# 20813.net
KiCad netlist of a schematic drawn in Altium Designer
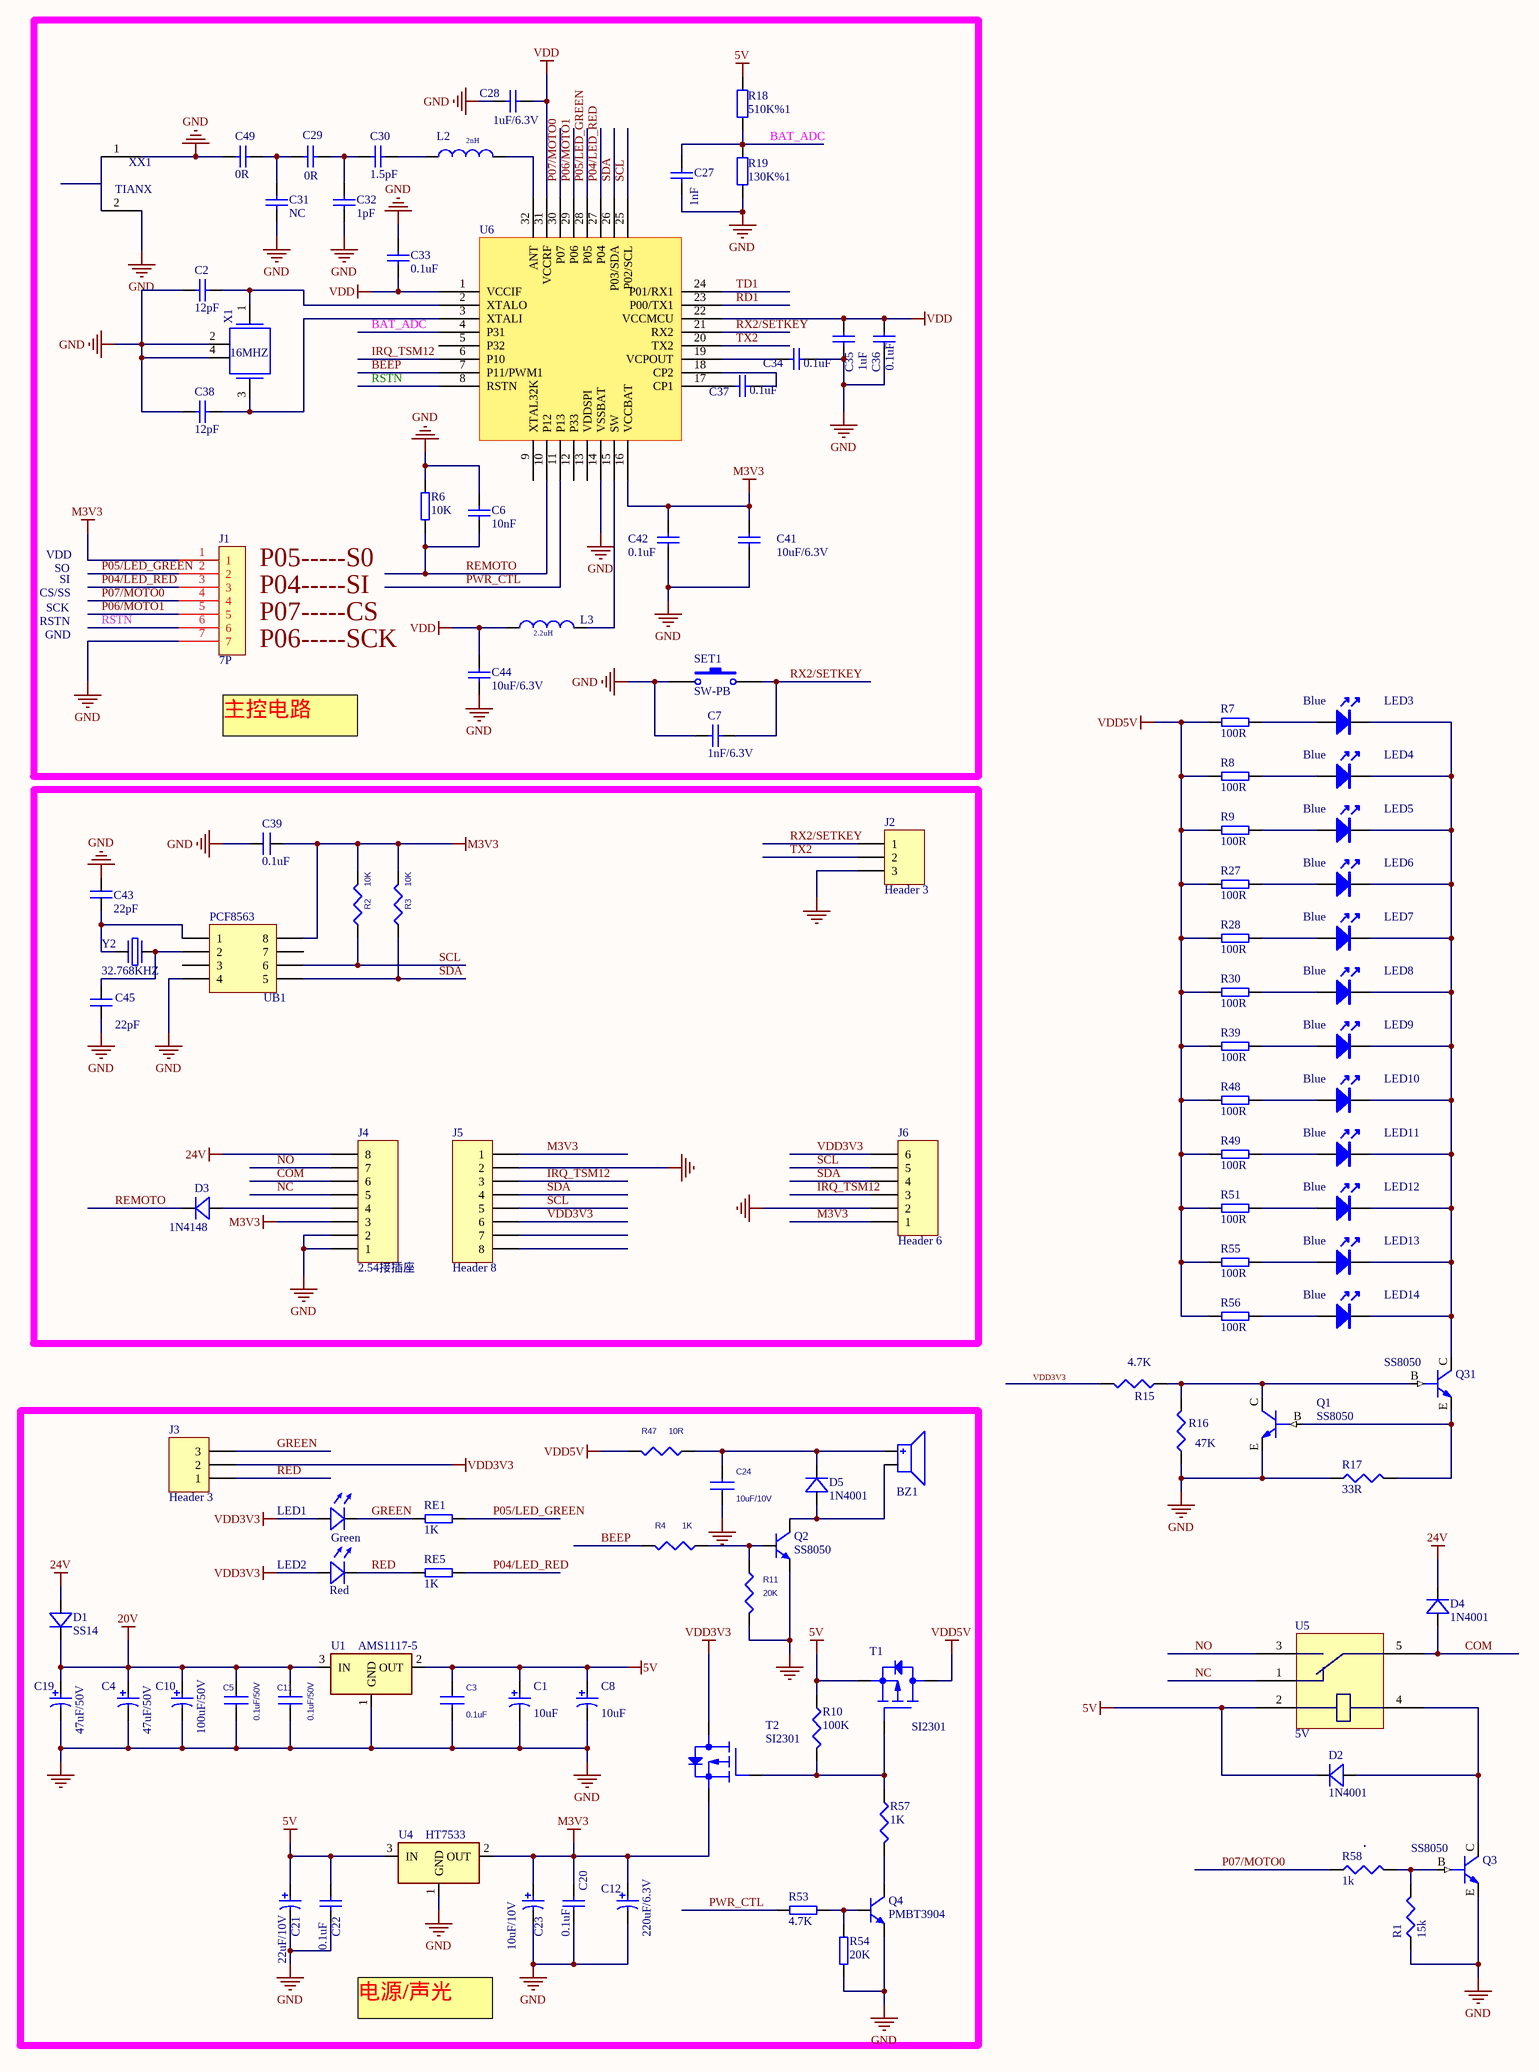
[diagram p0: 天地通门禁20813.SchDoc]

(export (version "E")
  (design (tool "Eeschema 10.0.6"))
  (components
    (comp (ref "BZ1")
      (value "BUZZER")
      (footprint "BUZZ_EN")
      (description "Buzzer")
      (libsource (lib "MyLibrary") (part "BUZZER"))
    )
    (comp (ref "C1")
      (value "10uF")
      (footprint "R6.3*5.8")
      (description "Capacitor, tolerance ±20%")
      (libsource (lib "MySchLib") (part "CAP-P"))
    )
    (comp (ref "C2")
      (value "12pF")
      (footprint "0603C")
      (description "Capacitor")
      (fields (field (name "PUBLISHER") "Altium Limited"))
      (libsource (lib "MySchlib") (part "Cap"))
    )
    (comp (ref "C3") (value "0.1uF") (footprint "0603C") (libsource (lib "*") (part "CAP NP")))
    (comp (ref "C4")
      (value "47uF/50V")
      (footprint "R6.3*7.7")
      (description "Capacitor, tolerance ±20%")
      (libsource (lib "MySchLib") (part "CAP-P"))
    )
    (comp (ref "C5") (value "0.1uF/50V") (footprint "0805C") (libsource (lib "*") (part "CAP NP")))
    (comp (ref "C6")
      (value "10nF")
      (footprint "0603C")
      (description "Capacitor")
      (fields (field (name "PUBLISHER") "Altium Limited"))
      (libsource (lib "MySchlib") (part "Cap"))
    )
    (comp (ref "C7")
      (value "1nF/6.3V")
      (footprint "0603C")
      (description "Capacitor")
      (fields (field (name "PUBLISHER") "Altium Limited"))
      (libsource (lib "MySchlib") (part "Cap"))
    )
    (comp (ref "C8")
      (value "10uF")
      (footprint "0805C")
      (description "Capacitor, tolerance ±20%")
      (libsource (lib "MySchLib") (part "CAP-P"))
    )
    (comp (ref "C10")
      (value "100uF/50V")
      (footprint "R6.3*7.7")
      (description "Capacitor, tolerance ±20%")
      (libsource (lib "MySchLib") (part "CAP-P"))
    )
    (comp (ref "C11") (value "0.1uF/50V") (footprint "0805C") (libsource (lib "*") (part "CAP NP")))
    (comp (ref "C12")
      (value "220uF/6.3V")
      (footprint "R6.3*5.8")
      (description "Capacitor, tolerance ±20%")
      (libsource (lib "MySchLib") (part "CAP-P"))
    )
    (comp (ref "C19")
      (value "47uF/50V")
      (footprint "R6.3*7.7")
      (description "Capacitor, tolerance ±20%")
      (libsource (lib "MySchLib") (part "CAP-P"))
    )
    (comp (ref "C20")
      (value "0.1uF")
      (footprint "0603C")
      (description "Capacitor, Ceramic")
      (fields (field (name "TOLERANCE") "5 %"))
      (libsource (lib "MyLibrary") (part "CAP-NP"))
    )
    (comp (ref "C21")
      (value "22uF/10V")
      (footprint "0805C")
      (description "Capacitor, tolerance ±20%")
      (libsource (lib "MySchLib") (part "CAP-P"))
    )
    (comp (ref "C22")
      (value "0.1uF")
      (footprint "0603C")
      (description "Capacitor, Ceramic")
      (fields (field (name "TOLERANCE") "5 %"))
      (libsource (lib "MyLibrary") (part "CAP-NP"))
    )
    (comp (ref "C23")
      (value "10uF/10V")
      (footprint "0805C")
      (description "Capacitor, tolerance ±20%")
      (libsource (lib "MySchLib") (part "CAP-P"))
    )
    (comp (ref "C24") (value "10uF/10V") (footprint "0805C") (libsource (lib "*") (part "C_0_Dup1")))
    (comp (ref "C27")
      (value "1nF")
      (footprint "0603C")
      (description "Capacitor, Ceramic")
      (fields (field (name "TOLERANCE") "5 %"))
      (libsource (lib "MyLibrary") (part "CAP-NP"))
    )
    (comp (ref "C28")
      (value "1uF/6.3V")
      (footprint "0603C")
      (description "Capacitor")
      (fields (field (name "PUBLISHER") "Altium Limited"))
      (libsource (lib "MySchlib") (part "Cap"))
    )
    (comp (ref "C29")
      (value "0R")
      (footprint "0603C")
      (description "Capacitor")
      (fields (field (name "PUBLISHER") "Altium Limited"))
      (libsource (lib "MySchlib") (part "Cap"))
    )
    (comp (ref "C30")
      (value "1.5pF")
      (footprint "0603C")
      (description "Capacitor")
      (fields (field (name "PUBLISHER") "Altium Limited"))
      (libsource (lib "MySchlib") (part "Cap"))
    )
    (comp (ref "C31")
      (value "NC")
      (footprint "0603C")
      (description "Capacitor")
      (fields (field (name "PUBLISHER") "Altium Limited"))
      (libsource (lib "MySchlib") (part "Cap"))
    )
    (comp (ref "C32")
      (value "1pF")
      (footprint "0603C")
      (description "Capacitor")
      (fields (field (name "PUBLISHER") "Altium Limited"))
      (libsource (lib "MySchlib") (part "Cap"))
    )
    (comp (ref "C33")
      (value "0.1uF")
      (footprint "0603C")
      (description "Capacitor")
      (fields (field (name "PUBLISHER") "Altium Limited"))
      (libsource (lib "MySchlib") (part "Cap"))
    )
    (comp (ref "C34")
      (value "0.1uF")
      (footprint "0603C")
      (description "Capacitor")
      (fields (field (name "PUBLISHER") "Altium Limited"))
      (libsource (lib "MySchlib") (part "Cap"))
    )
    (comp (ref "C35")
      (value "1uF")
      (footprint "0603C")
      (description "Capacitor")
      (fields (field (name "PUBLISHER") "Altium Limited"))
      (libsource (lib "MySchlib") (part "Cap"))
    )
    (comp (ref "C36")
      (value "0.1uF")
      (footprint "0603C")
      (description "Capacitor")
      (fields (field (name "PUBLISHER") "Altium Limited"))
      (libsource (lib "MySchlib") (part "Cap"))
    )
    (comp (ref "C37")
      (value "0.1uF")
      (footprint "0603C")
      (description "Capacitor")
      (fields (field (name "PUBLISHER") "Altium Limited"))
      (libsource (lib "MySchlib") (part "Cap"))
    )
    (comp (ref "C38")
      (value "12pF")
      (footprint "0603C")
      (description "Capacitor")
      (fields (field (name "PUBLISHER") "Altium Limited"))
      (libsource (lib "MySchlib") (part "Cap"))
    )
    (comp (ref "C39") (value "0.1uF") (footprint "0603C") (libsource (lib "自建元件库") (part "C")))
    (comp (ref "C41")
      (value "10uF/6.3V")
      (footprint "0603C")
      (description "Capacitor")
      (fields (field (name "PUBLISHER") "Altium Limited"))
      (libsource (lib "MySchlib") (part "Cap"))
    )
    (comp (ref "C42")
      (value "0.1uF")
      (footprint "0603C")
      (description "Capacitor")
      (fields (field (name "PUBLISHER") "Altium Limited"))
      (libsource (lib "MySchlib") (part "Cap"))
    )
    (comp (ref "C43") (value "22pF") (footprint "0603C") (libsource (lib "自建元件库") (part "C")))
    (comp (ref "C44")
      (value "10uF/6.3V")
      (footprint "0603C")
      (description "Capacitor")
      (fields (field (name "PUBLISHER") "Altium Limited"))
      (libsource (lib "MySchlib") (part "Cap"))
    )
    (comp (ref "C45") (value "22pF") (footprint "0603C") (libsource (lib "自建元件库") (part "C")))
    (comp (ref "C49")
      (value "0R")
      (footprint "0603C")
      (description "Capacitor")
      (fields (field (name "PUBLISHER") "Altium Limited"))
      (libsource (lib "MySchlib") (part "Cap"))
    )
    (comp (ref "D1") (value "SS14") (footprint "DO-214AA") (libsource (lib "") (part "D_1")))
    (comp (ref "D2") (value "1N4001") (footprint "M7") (libsource (lib "MySch") (part "D")))
    (comp (ref "D3") (value "1N4148") (footprint "SOD-123") (libsource (lib "") (part "D_1")))
    (comp (ref "D4") (value "1N4001") (footprint "M7") (libsource (lib "MySch") (part "D")))
    (comp (ref "D5") (value "1N4001") (footprint "M7") (libsource (lib "MySch") (part "D")))
    (comp (ref "J1") (value "7P") (footprint "7P-2.0MM") (libsource (lib "保险箱STM32") (part "7P")))
    (comp (ref "J2")
      (value "Header 3")
      (footprint "3P-2.0MM")
      (description "Header, 3-Pin")
      (fields (field (name "PUBLISHER") "Altium Limited"))
      (libsource (lib "Miscellaneous Connectors") (part "Header 3"))
    )
    (comp (ref "J3")
      (value "Header 3")
      (footprint "3PIN-2.0")
      (description "Header, 3-Pin")
      (fields (field (name "PUBLISHER") "Altium Limited"))
      (libsource (lib "") (part "Header 3_1"))
    )
    (comp (ref "J4")
      (value "2.54接插座")
      (footprint "2.54螺丝接线座8P")
      (description "Header, 8-Pin")
      (fields (field (name "PUBLISHER") "Altium Limited"))
      (libsource (lib "") (part "Header 8_1"))
    )
    (comp (ref "J5")
      (value "Header 8")
      (footprint "8P-1.25mm")
      (description "Header, 8-Pin")
      (fields (field (name "PUBLISHER") "Altium Limited"))
      (libsource (lib "Miscellaneous Connectors") (part "Header 8"))
    )
    (comp (ref "J6")
      (value "Header 6")
      (footprint "6P-1.25mm")
      (description "Header, 6-Pin")
      (fields (field (name "PUBLISHER") "Altium Limited"))
      (libsource (lib "Miscellaneous Connectors") (part "Header 6"))
    )
    (comp (ref "L2")
      (value "2nH")
      (footprint "0603L")
      (description "Power Inductor, 4.7uH, 0.7A, 260mR DCR")
      (fields
        (field (name "XMOS PART NUMBER") "E-09-0011")
        (field (name "MANUFACTURER") "Taiyo Yuden")
        (field (name "PART CREATOR") "JG")
        (field (name "APPROVED") "NO")
      )
      (libsource (lib "MySchlib") (part "INDUCTOR"))
    )
    (comp (ref "L3")
      (value "2.2uH")
      (footprint "0603L")
      (description "Power Inductor, 4.7uH, 0.7A, 260mR DCR")
      (fields
        (field (name "XMOS PART NUMBER") "E-09-0011")
        (field (name "MANUFACTURER") "Taiyo Yuden")
        (field (name "PART CREATOR") "JG")
        (field (name "APPROVED") "NO")
      )
      (libsource (lib "MySchlib") (part "INDUCTOR"))
    )
    (comp (ref "LED1") (value "Green") (footprint "0805LED") (libsource (lib "MyLibrary") (part "LED")))
    (comp (ref "LED2") (value "Red") (footprint "0805LED") (libsource (lib "MyLibrary") (part "LED")))
    (comp (ref "LED3") (value "Blue") (footprint "0805LED") (libsource (lib "*") (part "LED")))
    (comp (ref "LED4") (value "Blue") (footprint "0805LED") (libsource (lib "*") (part "LED")))
    (comp (ref "LED5") (value "Blue") (footprint "0805LED") (libsource (lib "*") (part "LED")))
    (comp (ref "LED6") (value "Blue") (footprint "0805LED") (libsource (lib "*") (part "LED")))
    (comp (ref "LED7") (value "Blue") (footprint "0805LED") (libsource (lib "*") (part "LED")))
    (comp (ref "LED8") (value "Blue") (footprint "0805LED") (libsource (lib "*") (part "LED")))
    (comp (ref "LED9") (value "Blue") (footprint "0805LED") (libsource (lib "*") (part "LED")))
    (comp (ref "LED10") (value "Blue") (footprint "0805LED") (libsource (lib "*") (part "LED")))
    (comp (ref "LED11") (value "Blue") (footprint "0805LED") (libsource (lib "*") (part "LED")))
    (comp (ref "LED12") (value "Blue") (footprint "0805LED") (libsource (lib "*") (part "LED")))
    (comp (ref "LED13") (value "Blue") (footprint "0805LED") (libsource (lib "*") (part "LED")))
    (comp (ref "LED14") (value "Blue") (footprint "0805LED") (libsource (lib "*") (part "LED")))
    (comp (ref "Q1") (value "SS8050") (footprint "SOT-23 - BCE") (libsource (lib "*") (part "PMBT3904")))
    (comp (ref "Q2")
      (value "SS8050")
      (footprint "SOT-23-3L")
      (description "Bipolar Junction Transistor")
      (libsource (lib "MyLibrary") (part "NPN_BJT"))
    )
    (comp (ref "Q3") (value "SS8050") (footprint "SOT-23 - BCE") (libsource (lib "*") (part "PMBT3904")))
    (comp (ref "Q4")
      (value "PMBT3904")
      (footprint "SOT-23-3L")
      (description "Bipolar Junction Transistor")
      (libsource (lib "MyLibrary") (part "NPN_BJT"))
    )
    (comp (ref "Q31") (value "SS8050") (footprint "SOT-23 - BCE") (libsource (lib "*") (part "PMBT3904")))
    (comp (ref "R1") (value "15k") (footprint "0603R") (libsource (lib "*") (part "R")))
    (comp (ref "R2") (value "10K") (footprint "0603R") (libsource (lib "*") (part "RES")))
    (comp (ref "R3") (value "10K") (footprint "0603R") (libsource (lib "*") (part "RES")))
    (comp (ref "R4") (value "1K") (footprint "0603R") (libsource (lib "*") (part "R_Dup1")))
    (comp (ref "R6") (value "10K") (footprint "0603R") (libsource (lib "MySch") (part "R")))
    (comp (ref "R7") (value "100R") (footprint "0603R") (libsource (lib "MySch") (part "R")))
    (comp (ref "R8") (value "100R") (footprint "0603R") (libsource (lib "MySch") (part "R")))
    (comp (ref "R9") (value "100R") (footprint "0603R") (libsource (lib "MySch") (part "R")))
    (comp (ref "R10") (value "100K") (footprint "0603R") (libsource (lib "*") (part "R")))
    (comp (ref "R11") (value "20K") (footprint "0603R") (libsource (lib "*") (part "R_Dup1")))
    (comp (ref "R15") (value "4.7K") (footprint "0603R") (libsource (lib "*") (part "R")))
    (comp (ref "R16") (value "47K") (footprint "0603R") (libsource (lib "*") (part "R")))
    (comp (ref "R17") (value "33R") (footprint "0603R") (libsource (lib "*") (part "R")))
    (comp (ref "R18")
      (value "510K%1")
      (footprint "0603R")
      (description "Resistor")
      (libsource (lib "MyLibrary") (part "Res2"))
    )
    (comp (ref "R19")
      (value "130K%1")
      (footprint "0603R")
      (description "Resistor")
      (libsource (lib "MyLibrary") (part "Res2"))
    )
    (comp (ref "R27") (value "100R") (footprint "0603R") (libsource (lib "MySch") (part "R")))
    (comp (ref "R28") (value "100R") (footprint "0603R") (libsource (lib "MySch") (part "R")))
    (comp (ref "R30") (value "100R") (footprint "0603R") (libsource (lib "MySch") (part "R")))
    (comp (ref "R39") (value "100R") (footprint "0603R") (libsource (lib "MySch") (part "R")))
    (comp (ref "R47") (value "10R") (footprint "0603R") (libsource (lib "*") (part "R_Dup1")))
    (comp (ref "R48") (value "100R") (footprint "0603R") (libsource (lib "MySch") (part "R")))
    (comp (ref "R49") (value "100R") (footprint "0603R") (libsource (lib "MySch") (part "R")))
    (comp (ref "R51") (value "100R") (footprint "0603R") (libsource (lib "MySch") (part "R")))
    (comp (ref "R53") (value "4.7K") (footprint "0603R") (libsource (lib "MySch") (part "R")))
    (comp (ref "R54") (value "20K") (footprint "0603R") (libsource (lib "MySch") (part "R")))
    (comp (ref "R55") (value "100R") (footprint "0603R") (libsource (lib "MySch") (part "R")))
    (comp (ref "R56") (value "100R") (footprint "0603R") (libsource (lib "MySch") (part "R")))
    (comp (ref "R57") (value "1K") (footprint "0603R") (libsource (lib "*") (part "R")))
    (comp (ref "R58") (value "1k") (footprint "0603R") (libsource (lib "*") (part "R")))
    (comp (ref "RE1") (value "1K") (footprint "0603R") (libsource (lib "MySch") (part "R")))
    (comp (ref "RE5") (value "1K") (footprint "0603R") (libsource (lib "MySch") (part "R")))
    (comp (ref "SET1")
      (value "SW-PB")
      (footprint "KEY-S")
      (description "Switch")
      (fields (field (name "PUBLISHER") "Altium Limited"))
      (libsource (lib "Miscellaneous Devices") (part "SW-PB"))
    )
    (comp (ref "T1")
      (value "SI2301")
      (footprint "SOT-23 - GDS")
      (libsource (lib "*") (part "PWRMOSFET_EP_DGS_0"))
    )
    (comp (ref "T2")
      (value "SI2301")
      (footprint "SOT-23 - GDS")
      (libsource (lib "*") (part "PWRMOSFET_EP_DGS_0"))
    )
    (comp (ref "U1") (value "AMS1117-5") (footprint "SOT223_M") (libsource (lib "*") (part "XC6206P302M")))
    (comp (ref "U4") (value "HT7533") (footprint "SOT-23-3L") (libsource (lib "*") (part "XC6206P302M")))
    (comp (ref "U5") (value "5V") (footprint "继电器1x") (libsource (lib "MYSchlib") (part "OMRON_G8P-1A4P")))
    (comp (ref "U6")
      (value "BK3431Q")
      (footprint "QFN32_4*4*0.4")
      (libsource (lib "BK3431") (part "BK3431Q"))
    )
    (comp (ref "UB1") (value "PCF8563") (footprint "SOP8") (libsource (lib "MySch") (part "IC8")))
    (comp (ref "X1")
      (value "16MHZ")
      (footprint "XTAL3225")
      (fields
        (field (name "XMOS PART NUMBER") "E-07-0030")
        (field (name "MANUFACTURER") "Abracon")
        (field (name "MANUFACTURER PART NUMBER") "ABLS-24.000MHz-B4")
        (field (name "PART CREATOR") "JG")
        (field (name "APPROVED") "NO")
      )
      (libsource (lib "MySchlib") (part "OSC"))
    )
    (comp (ref "XX1")
      (value "TIANX")
      (footprint "BT_NAMI_1")
      (libsource (lib "885阿里云PCB_Project1") (part "TIANX"))
    )
    (comp (ref "Y2") (value "32.768KHZ") (footprint "晶振-9") (libsource (lib "MySch") (part "晶振")))
  )
  (nets
    (net (code "1") (name "/BAT_ADC") (class "Default")
      (node (ref "C27") (pin "2") (pinfunction "2_2") (pintype "passive"))
      (node (ref "R18") (pin "2") (pinfunction "2_2") (pintype "passive"))
      (node (ref "R19") (pin "1") (pinfunction "1_1") (pintype "passive"))
      (node (ref "U6") (pin "4") (pinfunction "P31_4") (pintype "passive"))
    )
    (net (code "2") (name "/BEEP") (class "Default")
      (node (ref "R4") (pin "2") (pinfunction "2_2") (pintype "passive"))
      (node (ref "U6") (pin "7") (pinfunction "P11/PWM1_7") (pintype "passive"))
    )
    (net (code "3") (name "/COM") (class "Default")
      (node (ref "D4") (pin "A") (pinfunction "K_A") (pintype "passive"))
      (node (ref "J4") (pin "6") (pinfunction "6_6") (pintype "passive"))
      (node (ref "U5") (pin "5") (pinfunction "5_5") (pintype "passive"))
    )
    (net (code "4") (name "/GREEN") (class "Default")
      (node (ref "J3") (pin "3") (pinfunction "3_3") (pintype "passive"))
      (node (ref "LED1") (pin "2") (pinfunction "K_2") (pintype "passive"))
      (node (ref "RE1") (pin "1") (pintype "passive"))
    )
    (net (code "5") (name "/IRQ_TSM12") (class "Default")
      (node (ref "J5") (pin "3") (pinfunction "3_3") (pintype "passive"))
      (node (ref "J6") (pin "3") (pinfunction "3_3") (pintype "passive"))
      (node (ref "U6") (pin "6") (pinfunction "P10_6") (pintype "passive"))
    )
    (net (code "6") (name "/NC") (class "Default")
      (node (ref "J4") (pin "5") (pinfunction "5_5") (pintype "passive"))
      (node (ref "U5") (pin "1") (pinfunction "1_1") (pintype "passive"))
    )
    (net (code "7") (name "/NO") (class "Default")
      (node (ref "J4") (pin "7") (pinfunction "7_7") (pintype "passive"))
      (node (ref "U5") (pin "3") (pinfunction "3_3") (pintype "passive"))
    )
    (net (code "8") (name "/P04{slash}LED_RED") (class "Default")
      (node (ref "J1") (pin "3") (pinfunction "3_3") (pintype "passive"))
      (node (ref "RE5") (pin "2") (pintype "passive"))
      (node (ref "U6") (pin "27") (pinfunction "P04_27") (pintype "passive"))
    )
    (net (code "9") (name "/P05{slash}LED_GREEN") (class "Default")
      (node (ref "J1") (pin "2") (pinfunction "2_2") (pintype "passive"))
      (node (ref "RE1") (pin "2") (pintype "passive"))
      (node (ref "U6") (pin "28") (pinfunction "P05_28") (pintype "passive"))
    )
    (net (code "10") (name "/P06{slash}MOTO1") (class "Default")
      (node (ref "J1") (pin "5") (pinfunction "5_5") (pintype "passive"))
      (node (ref "U6") (pin "29") (pinfunction "P06_29") (pintype "passive"))
    )
    (net (code "11") (name "/P07{slash}MOTO0") (class "Default")
      (node (ref "J1") (pin "4") (pinfunction "4_4") (pintype "passive"))
      (node (ref "R58") (pin "1") (pinfunction "1_1") (pintype "passive"))
      (node (ref "U6") (pin "30") (pinfunction "P07_30") (pintype "passive"))
    )
    (net (code "12") (name "/PWR_CTL") (class "Default")
      (node (ref "R53") (pin "1") (pintype "passive"))
      (node (ref "U6") (pin "11") (pinfunction "P13_11") (pintype "passive"))
    )
    (net (code "13") (name "/RD1") (class "Default")
      (node (ref "U6") (pin "23") (pinfunction "P00/TX1_23") (pintype "passive"))
    )
    (net (code "14") (name "/RED") (class "Default")
      (node (ref "J3") (pin "1") (pinfunction "1_1") (pintype "passive"))
      (node (ref "LED2") (pin "2") (pinfunction "K_2") (pintype "passive"))
      (node (ref "RE5") (pin "1") (pintype "passive"))
    )
    (net (code "15") (name "/REMOTO") (class "Default")
      (node (ref "C6") (pin "2") (pinfunction "2_2") (pintype "passive"))
      (node (ref "D3") (pin "2") (pinfunction "K_2") (pintype "passive"))
      (node (ref "R6") (pin "1") (pintype "passive"))
      (node (ref "U6") (pin "10") (pinfunction "P12_10") (pintype "passive"))
    )
    (net (code "16") (name "/RSTN") (class "Default")
      (node (ref "J1") (pin "6") (pinfunction "6_6") (pintype "passive"))
      (node (ref "U6") (pin "8") (pinfunction "RSTN_8") (pintype "passive"))
    )
    (net (code "17") (name "/RX2{slash}SETKEY") (class "Default")
      (node (ref "C7") (pin "1") (pinfunction "1_1") (pintype "passive"))
      (node (ref "J2") (pin "1") (pinfunction "1_1") (pintype "passive"))
      (node (ref "SET1") (pin "2") (pinfunction "2_2") (pintype "passive"))
      (node (ref "U6") (pin "21") (pinfunction "RX2_21") (pintype "passive"))
    )
    (net (code "18") (name "/SCL") (class "Default")
      (node (ref "J5") (pin "5") (pinfunction "5_5") (pintype "passive"))
      (node (ref "J6") (pin "5") (pinfunction "5_5") (pintype "passive"))
      (node (ref "R2") (pin "2") (pinfunction "2_2") (pintype "passive"))
      (node (ref "U6") (pin "25") (pinfunction "P02/SCL_25") (pintype "passive"))
      (node (ref "UB1") (pin "6") (pinfunction "6_6") (pintype "passive"))
    )
    (net (code "19") (name "/SDA") (class "Default")
      (node (ref "J5") (pin "4") (pinfunction "4_4") (pintype "passive"))
      (node (ref "J6") (pin "4") (pinfunction "4_4") (pintype "passive"))
      (node (ref "R3") (pin "2") (pinfunction "2_2") (pintype "passive"))
      (node (ref "U6") (pin "26") (pinfunction "P03/SDA_26") (pintype "passive"))
      (node (ref "UB1") (pin "5") (pinfunction "5_5") (pintype "passive"))
    )
    (net (code "20") (name "/TD1") (class "Default")
      (node (ref "U6") (pin "24") (pinfunction "P01/RX1_24") (pintype "passive"))
    )
    (net (code "21") (name "/TX2") (class "Default")
      (node (ref "J2") (pin "2") (pinfunction "2_2") (pintype "passive"))
      (node (ref "U6") (pin "20") (pinfunction "TX2_20") (pintype "passive"))
    )
    (net (code "22") (name "5V") (class "Default")
      (node (ref "C1") (pin "1") (pinfunction "1_1") (pintype "passive"))
      (node (ref "C21") (pin "1") (pinfunction "1_1") (pintype "passive"))
      (node (ref "C22") (pin "1") (pinfunction "1_1") (pintype "passive"))
      (node (ref "C3") (pin "1") (pinfunction "1_1") (pintype "passive"))
      (node (ref "C8") (pin "1") (pinfunction "1_1") (pintype "passive"))
      (node (ref "D2") (pin "K") (pinfunction "A_K") (pintype "passive"))
      (node (ref "R10") (pin "1") (pinfunction "1_1") (pintype "passive"))
      (node (ref "R18") (pin "1") (pinfunction "1_1") (pintype "passive"))
      (node (ref "T1") (pin "S") (pinfunction "SOURCE_S") (pintype "passive"))
      (node (ref "U1") (pin "2") (pinfunction "OUT_2") (pintype "passive"))
      (node (ref "U4") (pin "3") (pinfunction "IN_3") (pintype "passive"))
      (node (ref "U5") (pin "2") (pinfunction "2_2") (pintype "passive"))
    )
    (net (code "23") (name "20V") (class "Default")
      (node (ref "C10") (pin "1") (pinfunction "1_1") (pintype "passive"))
      (node (ref "C11") (pin "1") (pinfunction "1_1") (pintype "passive"))
      (node (ref "C19") (pin "1") (pinfunction "1_1") (pintype "passive"))
      (node (ref "C4") (pin "1") (pinfunction "1_1") (pintype "passive"))
      (node (ref "C5") (pin "1") (pinfunction "1_1") (pintype "passive"))
      (node (ref "D1") (pin "2") (pinfunction "K_2") (pintype "passive"))
      (node (ref "U1") (pin "3") (pinfunction "IN_3") (pintype "passive"))
    )
    (net (code "24") (name "24V") (class "Default")
      (node (ref "D1") (pin "1") (pinfunction "A_1") (pintype "passive"))
      (node (ref "D4") (pin "K") (pinfunction "A_K") (pintype "passive"))
      (node (ref "J4") (pin "8") (pinfunction "8_8") (pintype "passive"))
    )
    (net (code "25") (name "GND") (class "Default")
      (node (ref "C1") (pin "2") (pinfunction "2_2") (pintype "passive"))
      (node (ref "C10") (pin "2") (pinfunction "2_2") (pintype "passive"))
      (node (ref "C11") (pin "2") (pinfunction "2_2") (pintype "passive"))
      (node (ref "C12") (pin "2") (pinfunction "2_2") (pintype "passive"))
      (node (ref "C19") (pin "2") (pinfunction "2_2") (pintype "passive"))
      (node (ref "C2") (pin "1") (pinfunction "1_1") (pintype "passive"))
      (node (ref "C20") (pin "2") (pinfunction "2_2") (pintype "passive"))
      (node (ref "C21") (pin "2") (pinfunction "2_2") (pintype "passive"))
      (node (ref "C22") (pin "2") (pinfunction "2_2") (pintype "passive"))
      (node (ref "C23") (pin "2") (pinfunction "2_2") (pintype "passive"))
      (node (ref "C24") (pin "1") (pinfunction "1_1") (pintype "passive"))
      (node (ref "C27") (pin "1") (pinfunction "1_1") (pintype "passive"))
      (node (ref "C28") (pin "1") (pinfunction "1_1") (pintype "passive"))
      (node (ref "C3") (pin "2") (pinfunction "2_2") (pintype "passive"))
      (node (ref "C31") (pin "2") (pinfunction "2_2") (pintype "passive"))
      (node (ref "C32") (pin "1") (pinfunction "1_1") (pintype "passive"))
      (node (ref "C33") (pin "1") (pinfunction "1_1") (pintype "passive"))
      (node (ref "C34") (pin "2") (pinfunction "2_2") (pintype "passive"))
      (node (ref "C35") (pin "1") (pinfunction "1_1") (pintype "passive"))
      (node (ref "C36") (pin "1") (pinfunction "1_1") (pintype "passive"))
      (node (ref "C38") (pin "1") (pinfunction "1_1") (pintype "passive"))
      (node (ref "C39") (pin "2") (pintype "passive"))
      (node (ref "C4") (pin "2") (pinfunction "2_2") (pintype "passive"))
      (node (ref "C41") (pin "2") (pinfunction "2_2") (pintype "passive"))
      (node (ref "C42") (pin "2") (pinfunction "2_2") (pintype "passive"))
      (node (ref "C43") (pin "2") (pintype "passive"))
      (node (ref "C44") (pin "1") (pinfunction "1_1") (pintype "passive"))
      (node (ref "C45") (pin "1") (pintype "passive"))
      (node (ref "C49") (pin "1") (pinfunction "1_1") (pintype "passive"))
      (node (ref "C5") (pin "2") (pinfunction "2_2") (pintype "passive"))
      (node (ref "C6") (pin "1") (pinfunction "1_1") (pintype "passive"))
      (node (ref "C7") (pin "2") (pinfunction "2_2") (pintype "passive"))
      (node (ref "C8") (pin "2") (pinfunction "2_2") (pintype "passive"))
      (node (ref "J1") (pin "7") (pinfunction "7_7") (pintype "passive"))
      (node (ref "J2") (pin "3") (pinfunction "3_3") (pintype "passive"))
      (node (ref "J4") (pin "1") (pinfunction "1_1") (pintype "passive"))
      (node (ref "J4") (pin "2") (pinfunction "2_2") (pintype "passive"))
      (node (ref "J5") (pin "2") (pinfunction "2_2") (pintype "passive"))
      (node (ref "J6") (pin "2") (pinfunction "2_2") (pintype "passive"))
      (node (ref "Q1") (pin "E") (pinfunction "EMITTER_E") (pintype "passive"))
      (node (ref "Q2") (pin "2") (pinfunction "2_2") (pintype "passive"))
      (node (ref "Q3") (pin "E") (pinfunction "EMITTER_E") (pintype "passive"))
      (node (ref "Q4") (pin "2") (pinfunction "2_2") (pintype "passive"))
      (node (ref "R1") (pin "1") (pinfunction "1_1") (pintype "passive"))
      (node (ref "R11") (pin "2") (pinfunction "2_2") (pintype "passive"))
      (node (ref "R16") (pin "1") (pinfunction "1_1") (pintype "passive"))
      (node (ref "R17") (pin "1") (pinfunction "1_1") (pintype "passive"))
      (node (ref "R19") (pin "2") (pinfunction "2_2") (pintype "passive"))
      (node (ref "R54") (pin "1") (pintype "passive"))
      (node (ref "R6") (pin "2") (pintype "passive"))
      (node (ref "SET1") (pin "1") (pinfunction "1_1") (pintype "passive"))
      (node (ref "U1") (pin "1") (pinfunction "GND_1") (pintype "passive"))
      (node (ref "U4") (pin "1") (pinfunction "GND_1") (pintype "passive"))
      (node (ref "U6") (pin "14") (pinfunction "VSSBAT_14") (pintype "passive"))
      (node (ref "UB1") (pin "4") (pinfunction "4_4") (pintype "passive"))
      (node (ref "X1") (pin "2") (pintype "passive"))
      (node (ref "X1") (pin "4") (pintype "passive"))
      (node (ref "XX1") (pin "1") (pinfunction "1_1") (pintype "passive"))
      (node (ref "XX1") (pin "2") (pinfunction "2_2") (pintype "passive"))
    )
    (net (code "26") (name "M3V3") (class "Default")
      (node (ref "C12") (pin "1") (pinfunction "1_1") (pintype "passive"))
      (node (ref "C20") (pin "1") (pinfunction "1_1") (pintype "passive"))
      (node (ref "C23") (pin "1") (pinfunction "1_1") (pintype "passive"))
      (node (ref "C39") (pin "1") (pintype "passive"))
      (node (ref "C41") (pin "1") (pinfunction "1_1") (pintype "passive"))
      (node (ref "C42") (pin "1") (pinfunction "1_1") (pintype "passive"))
      (node (ref "J1") (pin "1") (pinfunction "1_1") (pintype "passive"))
      (node (ref "J4") (pin "3") (pinfunction "3_3") (pintype "passive"))
      (node (ref "J5") (pin "1") (pinfunction "1_1") (pintype "passive"))
      (node (ref "J6") (pin "1") (pinfunction "1_1") (pintype "passive"))
      (node (ref "R2") (pin "1") (pinfunction "1_1") (pintype "passive"))
      (node (ref "R3") (pin "1") (pinfunction "1_1") (pintype "passive"))
      (node (ref "T2") (pin "S") (pinfunction "SOURCE_S") (pintype "passive"))
      (node (ref "U4") (pin "2") (pinfunction "OUT_2") (pintype "passive"))
      (node (ref "U6") (pin "16") (pinfunction "VCCBAT_16") (pintype "passive"))
      (node (ref "UB1") (pin "8") (pinfunction "8_8") (pintype "passive"))
    )
    (net (code "27") (name "Net-(C29-Pad1)") (class "Default")
      (node (ref "C29") (pin "1") (pinfunction "1_1") (pintype "passive"))
      (node (ref "C31") (pin "1") (pinfunction "1_1") (pintype "passive"))
      (node (ref "C49") (pin "2") (pinfunction "2_2") (pintype "passive"))
    )
    (net (code "28") (name "Net-(C29-Pad2)") (class "Default")
      (node (ref "C29") (pin "2") (pinfunction "2_2") (pintype "passive"))
      (node (ref "C30") (pin "2") (pinfunction "2_2") (pintype "passive"))
      (node (ref "C32") (pin "2") (pinfunction "2_2") (pintype "passive"))
    )
    (net (code "29") (name "Net-(C43-Pad1)") (class "Default")
      (node (ref "C43") (pin "1") (pintype "passive"))
      (node (ref "UB1") (pin "1") (pinfunction "1_1") (pintype "passive"))
      (node (ref "Y2") (pin "2") (pintype "passive"))
    )
    (net (code "30") (name "Net-(C45-Pad2)") (class "Default")
      (node (ref "C45") (pin "2") (pintype "passive"))
      (node (ref "UB1") (pin "2") (pinfunction "2_2") (pintype "passive"))
      (node (ref "Y2") (pin "1") (pintype "passive"))
    )
    (net (code "31") (name "Net-(D2-K)") (class "Default")
      (node (ref "D2") (pin "A") (pinfunction "K_A") (pintype "passive"))
      (node (ref "Q3") (pin "C") (pinfunction "COLLECTOR_C") (pintype "passive"))
      (node (ref "U5") (pin "4") (pinfunction "4_4") (pintype "passive"))
    )
    (net (code "32") (name "Net-(D3-A)") (class "Default")
      (node (ref "D3") (pin "1") (pinfunction "A_1") (pintype "passive"))
      (node (ref "J4") (pin "4") (pinfunction "4_4") (pintype "passive"))
    )
    (net (code "33") (name "Net-(D5-A)") (class "Default")
      (node (ref "BZ1") (pin "1") (pintype "passive"))
      (node (ref "C24") (pin "2") (pinfunction "2_2") (pintype "passive"))
      (node (ref "D5") (pin "K") (pinfunction "A_K") (pintype "passive"))
      (node (ref "R47") (pin "1") (pinfunction "1_1") (pintype "passive"))
    )
    (net (code "34") (name "Net-(D5-K)") (class "Default")
      (node (ref "BZ1") (pin "2") (pintype "passive"))
      (node (ref "D5") (pin "A") (pinfunction "K_A") (pintype "passive"))
      (node (ref "Q2") (pin "3") (pinfunction "3_3") (pintype "passive"))
    )
    (net (code "35") (name "Net-(L2-P1)") (class "Default")
      (node (ref "C30") (pin "1") (pinfunction "1_1") (pintype "passive"))
      (node (ref "L2") (pin "1") (pinfunction "P1_1") (pintype "passive"))
    )
    (net (code "36") (name "Net-(L2-P2)") (class "Default")
      (node (ref "L2") (pin "2") (pinfunction "P2_2") (pintype "passive"))
      (node (ref "U6") (pin "32") (pinfunction "ANT_32") (pintype "passive"))
    )
    (net (code "37") (name "Net-(L3-P2)") (class "Default")
      (node (ref "L3") (pin "2") (pinfunction "P2_2") (pintype "passive"))
      (node (ref "U6") (pin "15") (pinfunction "SW_15") (pintype "passive"))
    )
    (net (code "38") (name "Net-(LED3-Pad1)") (class "Default")
      (node (ref "LED3") (pin "1") (pinfunction "1_1") (pintype "passive"))
      (node (ref "R7") (pin "2") (pintype "passive"))
    )
    (net (code "39") (name "Net-(LED4-Pad1)") (class "Default")
      (node (ref "LED4") (pin "1") (pinfunction "1_1") (pintype "passive"))
      (node (ref "R8") (pin "2") (pintype "passive"))
    )
    (net (code "40") (name "Net-(LED5-Pad1)") (class "Default")
      (node (ref "LED5") (pin "1") (pinfunction "1_1") (pintype "passive"))
      (node (ref "R9") (pin "2") (pintype "passive"))
    )
    (net (code "41") (name "Net-(LED6-Pad1)") (class "Default")
      (node (ref "LED6") (pin "1") (pinfunction "1_1") (pintype "passive"))
      (node (ref "R27") (pin "2") (pintype "passive"))
    )
    (net (code "42") (name "Net-(LED7-Pad1)") (class "Default")
      (node (ref "LED7") (pin "1") (pinfunction "1_1") (pintype "passive"))
      (node (ref "R28") (pin "2") (pintype "passive"))
    )
    (net (code "43") (name "Net-(LED8-Pad1)") (class "Default")
      (node (ref "LED8") (pin "1") (pinfunction "1_1") (pintype "passive"))
      (node (ref "R30") (pin "2") (pintype "passive"))
    )
    (net (code "44") (name "Net-(LED9-Pad1)") (class "Default")
      (node (ref "LED9") (pin "1") (pinfunction "1_1") (pintype "passive"))
      (node (ref "R39") (pin "2") (pintype "passive"))
    )
    (net (code "45") (name "Net-(LED10-Pad1)") (class "Default")
      (node (ref "LED10") (pin "1") (pinfunction "1_1") (pintype "passive"))
      (node (ref "R48") (pin "2") (pintype "passive"))
    )
    (net (code "46") (name "Net-(LED11-Pad1)") (class "Default")
      (node (ref "LED11") (pin "1") (pinfunction "1_1") (pintype "passive"))
      (node (ref "R49") (pin "2") (pintype "passive"))
    )
    (net (code "47") (name "Net-(LED12-Pad1)") (class "Default")
      (node (ref "LED12") (pin "1") (pinfunction "1_1") (pintype "passive"))
      (node (ref "R51") (pin "2") (pintype "passive"))
    )
    (net (code "48") (name "Net-(LED13-Pad1)") (class "Default")
      (node (ref "LED13") (pin "1") (pinfunction "1_1") (pintype "passive"))
      (node (ref "R55") (pin "2") (pintype "passive"))
    )
    (net (code "49") (name "Net-(LED14-Pad1)") (class "Default")
      (node (ref "LED14") (pin "1") (pinfunction "1_1") (pintype "passive"))
      (node (ref "R56") (pin "2") (pintype "passive"))
    )
    (net (code "50") (name "Net-(Q1-BASE)") (class "Default")
      (node (ref "Q1") (pin "B") (pinfunction "BASE_B") (pintype "input"))
      (node (ref "Q31") (pin "E") (pinfunction "EMITTER_E") (pintype "passive"))
      (node (ref "R17") (pin "2") (pinfunction "2_2") (pintype "passive"))
    )
    (net (code "51") (name "Net-(Q1-COLLECTOR)") (class "Default")
      (node (ref "Q1") (pin "C") (pinfunction "COLLECTOR_C") (pintype "passive"))
      (node (ref "Q31") (pin "B") (pinfunction "BASE_B") (pintype "input"))
      (node (ref "R15") (pin "1") (pinfunction "1_1") (pintype "passive"))
      (node (ref "R16") (pin "2") (pinfunction "2_2") (pintype "passive"))
    )
    (net (code "52") (name "Net-(Q2-Pad1)") (class "Default")
      (node (ref "Q2") (pin "1") (pinfunction "1_1") (pintype "passive"))
      (node (ref "R11") (pin "1") (pinfunction "1_1") (pintype "passive"))
      (node (ref "R4") (pin "1") (pinfunction "1_1") (pintype "passive"))
    )
    (net (code "53") (name "Net-(Q3-BASE)") (class "Default")
      (node (ref "Q3") (pin "B") (pinfunction "BASE_B") (pintype "input"))
      (node (ref "R1") (pin "2") (pinfunction "2_2") (pintype "passive"))
      (node (ref "R58") (pin "2") (pinfunction "2_2") (pintype "passive"))
    )
    (net (code "54") (name "Net-(Q4-Pad1)") (class "Default")
      (node (ref "Q4") (pin "1") (pinfunction "1_1") (pintype "passive"))
      (node (ref "R53") (pin "2") (pintype "passive"))
      (node (ref "R54") (pin "2") (pintype "passive"))
    )
    (net (code "55") (name "Net-(Q4-Pad3)") (class "Default")
      (node (ref "Q4") (pin "3") (pinfunction "3_3") (pintype "passive"))
      (node (ref "R57") (pin "2") (pinfunction "2_2") (pintype "passive"))
    )
    (net (code "56") (name "Net-(Q31-COLLECTOR)") (class "Default")
      (node (ref "LED10") (pin "2") (pinfunction "2_2") (pintype "passive"))
      (node (ref "LED11") (pin "2") (pinfunction "2_2") (pintype "passive"))
      (node (ref "LED12") (pin "2") (pinfunction "2_2") (pintype "passive"))
      (node (ref "LED13") (pin "2") (pinfunction "2_2") (pintype "passive"))
      (node (ref "LED14") (pin "2") (pinfunction "2_2") (pintype "passive"))
      (node (ref "LED3") (pin "2") (pinfunction "2_2") (pintype "passive"))
      (node (ref "LED4") (pin "2") (pinfunction "2_2") (pintype "passive"))
      (node (ref "LED5") (pin "2") (pinfunction "2_2") (pintype "passive"))
      (node (ref "LED6") (pin "2") (pinfunction "2_2") (pintype "passive"))
      (node (ref "LED7") (pin "2") (pinfunction "2_2") (pintype "passive"))
      (node (ref "LED8") (pin "2") (pinfunction "2_2") (pintype "passive"))
      (node (ref "LED9") (pin "2") (pinfunction "2_2") (pintype "passive"))
      (node (ref "Q31") (pin "C") (pinfunction "COLLECTOR_C") (pintype "passive"))
    )
    (net (code "57") (name "Net-(T1-GATE)") (class "Default")
      (node (ref "R10") (pin "2") (pinfunction "2_2") (pintype "passive"))
      (node (ref "R57") (pin "1") (pinfunction "1_1") (pintype "passive"))
      (node (ref "T1") (pin "G") (pinfunction "GATE_G") (pintype "passive"))
      (node (ref "T2") (pin "G") (pinfunction "GATE_G") (pintype "passive"))
    )
    (net (code "58") (name "Net-(U6-CP1)") (class "Default")
      (node (ref "C37") (pin "1") (pinfunction "1_1") (pintype "passive"))
      (node (ref "U6") (pin "17") (pinfunction "CP1_17") (pintype "passive"))
    )
    (net (code "59") (name "Net-(U6-CP2)") (class "Default")
      (node (ref "C37") (pin "2") (pinfunction "2_2") (pintype "passive"))
      (node (ref "U6") (pin "18") (pinfunction "CP2_18") (pintype "passive"))
    )
    (net (code "60") (name "Net-(U6-VCPOUT)") (class "Default")
      (node (ref "C34") (pin "1") (pinfunction "1_1") (pintype "passive"))
      (node (ref "U6") (pin "19") (pinfunction "VCPOUT_19") (pintype "passive"))
    )
    (net (code "61") (name "Net-(U6-XTALI)") (class "Default")
      (node (ref "C38") (pin "2") (pinfunction "2_2") (pintype "passive"))
      (node (ref "U6") (pin "3") (pinfunction "XTALI_3") (pintype "passive"))
      (node (ref "X1") (pin "3") (pintype "passive"))
    )
    (net (code "62") (name "Net-(U6-XTALO)") (class "Default")
      (node (ref "C2") (pin "2") (pinfunction "2_2") (pintype "passive"))
      (node (ref "U6") (pin "2") (pinfunction "XTALO_2") (pintype "passive"))
      (node (ref "X1") (pin "1") (pintype "passive"))
    )
    (net (code "63") (name "VDD") (class "Default")
      (node (ref "C28") (pin "2") (pinfunction "2_2") (pintype "passive"))
      (node (ref "C33") (pin "2") (pinfunction "2_2") (pintype "passive"))
      (node (ref "C35") (pin "2") (pinfunction "2_2") (pintype "passive"))
      (node (ref "C36") (pin "2") (pinfunction "2_2") (pintype "passive"))
      (node (ref "C44") (pin "2") (pinfunction "2_2") (pintype "passive"))
      (node (ref "L3") (pin "1") (pinfunction "P1_1") (pintype "passive"))
      (node (ref "U6") (pin "1") (pinfunction "VCCIF_1") (pintype "passive"))
      (node (ref "U6") (pin "22") (pinfunction "VCCMCU_22") (pintype "passive"))
      (node (ref "U6") (pin "31") (pinfunction "VCCRF_31") (pintype "passive"))
    )
    (net (code "64") (name "VDD3V3") (class "Default")
      (node (ref "J3") (pin "2") (pinfunction "2_2") (pintype "passive"))
      (node (ref "J5") (pin "6") (pinfunction "6_6") (pintype "passive"))
      (node (ref "J6") (pin "6") (pinfunction "6_6") (pintype "passive"))
      (node (ref "LED1") (pin "1") (pinfunction "A_1") (pintype "passive"))
      (node (ref "LED2") (pin "1") (pinfunction "A_1") (pintype "passive"))
      (node (ref "R15") (pin "2") (pinfunction "2_2") (pintype "passive"))
      (node (ref "T2") (pin "D") (pinfunction "DRAIN_D") (pintype "passive"))
    )
    (net (code "65") (name "VDD5V") (class "Default")
      (node (ref "R27") (pin "1") (pintype "passive"))
      (node (ref "R28") (pin "1") (pintype "passive"))
      (node (ref "R30") (pin "1") (pintype "passive"))
      (node (ref "R39") (pin "1") (pintype "passive"))
      (node (ref "R47") (pin "2") (pinfunction "2_2") (pintype "passive"))
      (node (ref "R48") (pin "1") (pintype "passive"))
      (node (ref "R49") (pin "1") (pintype "passive"))
      (node (ref "R51") (pin "1") (pintype "passive"))
      (node (ref "R55") (pin "1") (pintype "passive"))
      (node (ref "R56") (pin "1") (pintype "passive"))
      (node (ref "R7") (pin "1") (pintype "passive"))
      (node (ref "R8") (pin "1") (pintype "passive"))
      (node (ref "R9") (pin "1") (pintype "passive"))
      (node (ref "T1") (pin "D") (pinfunction "DRAIN_D") (pintype "passive"))
    )
    (net (code "66") (name "unconnected-(J5-Pad7)") (class "Default")
      (node (ref "J5") (pin "7") (pinfunction "7_7") (pintype "passive"))
    )
    (net (code "67") (name "unconnected-(J5-Pad8)") (class "Default")
      (node (ref "J5") (pin "8") (pinfunction "8_8") (pintype "passive"))
    )
    (net (code "68") (name "unconnected-(U6-P32-Pad5)") (class "Default")
      (node (ref "U6") (pin "5") (pinfunction "P32_5") (pintype "passive"))
    )
    (net (code "69") (name "unconnected-(U6-P33-Pad12)") (class "Default")
      (node (ref "U6") (pin "12") (pinfunction "P33_12") (pintype "passive"))
    )
    (net (code "70") (name "unconnected-(U6-VDDSPI-Pad13)") (class "Default")
      (node (ref "U6") (pin "13") (pinfunction "VDDSPI_13") (pintype "passive"))
    )
    (net (code "71") (name "unconnected-(U6-XTAL32K-Pad9)") (class "Default")
      (node (ref "U6") (pin "9") (pinfunction "XTAL32K_9") (pintype "passive"))
    )
    (net (code "72") (name "unconnected-(UB1-Pad3)") (class "Default")
      (node (ref "UB1") (pin "3") (pinfunction "3_3") (pintype "passive"))
    )
    (net (code "73") (name "unconnected-(UB1-Pad7)") (class "Default")
      (node (ref "UB1") (pin "7") (pinfunction "7_7") (pintype "passive"))
    )
  )
)
